# Digital_Input.net
KiCad netlist of a schematic drawn in Altium Designer
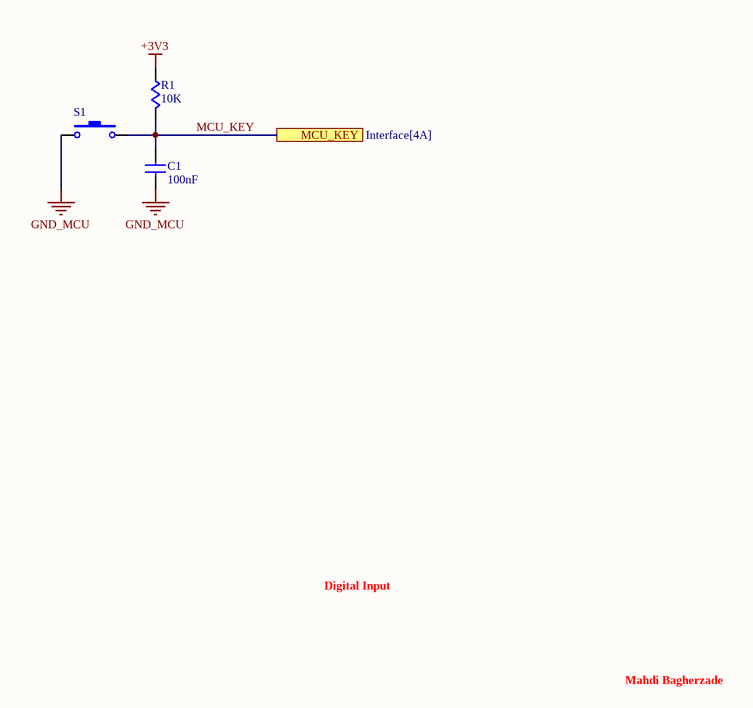
[diagram p0: Digital Input.SchDoc]

(export (version "E")
  (design (tool "Eeschema 10.0.6"))
  (components
    (comp (ref "C1")
      (value "100nF")
      (footprint "C-0805")
      (description "CAPACITOR")
      (fields
        (field (name "VOLTAGE") "50V")
        (field (name "TOLERANCE") "X7R")
        (field (name "PUBLISHER") "Mahdi Bagherzadeh")
      )
      (libsource (lib "Mahdi-Bagherzadeh") (part "CAP-CER"))
    )
    (comp (ref "R1")
      (value "10K")
      (footprint "R-0805")
      (description "RESISTOR")
      (fields
        (field (name "TOLERANCE") "5%")
        (field (name "POWER") "1/8W")
        (field (name "PUBLISHER") "Mahdi Bagherzadeh")
      )
      (libsource (lib "Mahdi-Bagherzadeh") (part "RES"))
    )
    (comp (ref "S1")
      (value "UP")
      (footprint "SW-SMD-2pin-3x6")
      (description "SWITCH")
      (fields (field (name "PUBLISHER") "Mahdi Bagherzadeh"))
      (libsource (lib "Mahdi-Bagherzadeh") (part "PUSH BUTTON"))
    )
  )
  (nets
    (net (code "1") (name "+3V3") (class "Default")
      (node (ref "R1") (pin "1") (pinfunction "1_1") (pintype "passive"))
    )
    (net (code "2") (name "/MCU_KEY") (class "Default")
      (node (ref "C1") (pin "1") (pinfunction "1_1") (pintype "passive"))
      (node (ref "R1") (pin "2") (pinfunction "2_2") (pintype "passive"))
      (node (ref "S1") (pin "2") (pinfunction "2_2") (pintype "passive"))
    )
    (net (code "3") (name "GND_MCU") (class "Default")
      (node (ref "C1") (pin "2") (pinfunction "2_2") (pintype "passive"))
      (node (ref "S1") (pin "1") (pinfunction "1_1") (pintype "passive"))
    )
  )
)
